# NoBattNVRAM.net
KiCad netlist of a schematic drawn in EAGLE
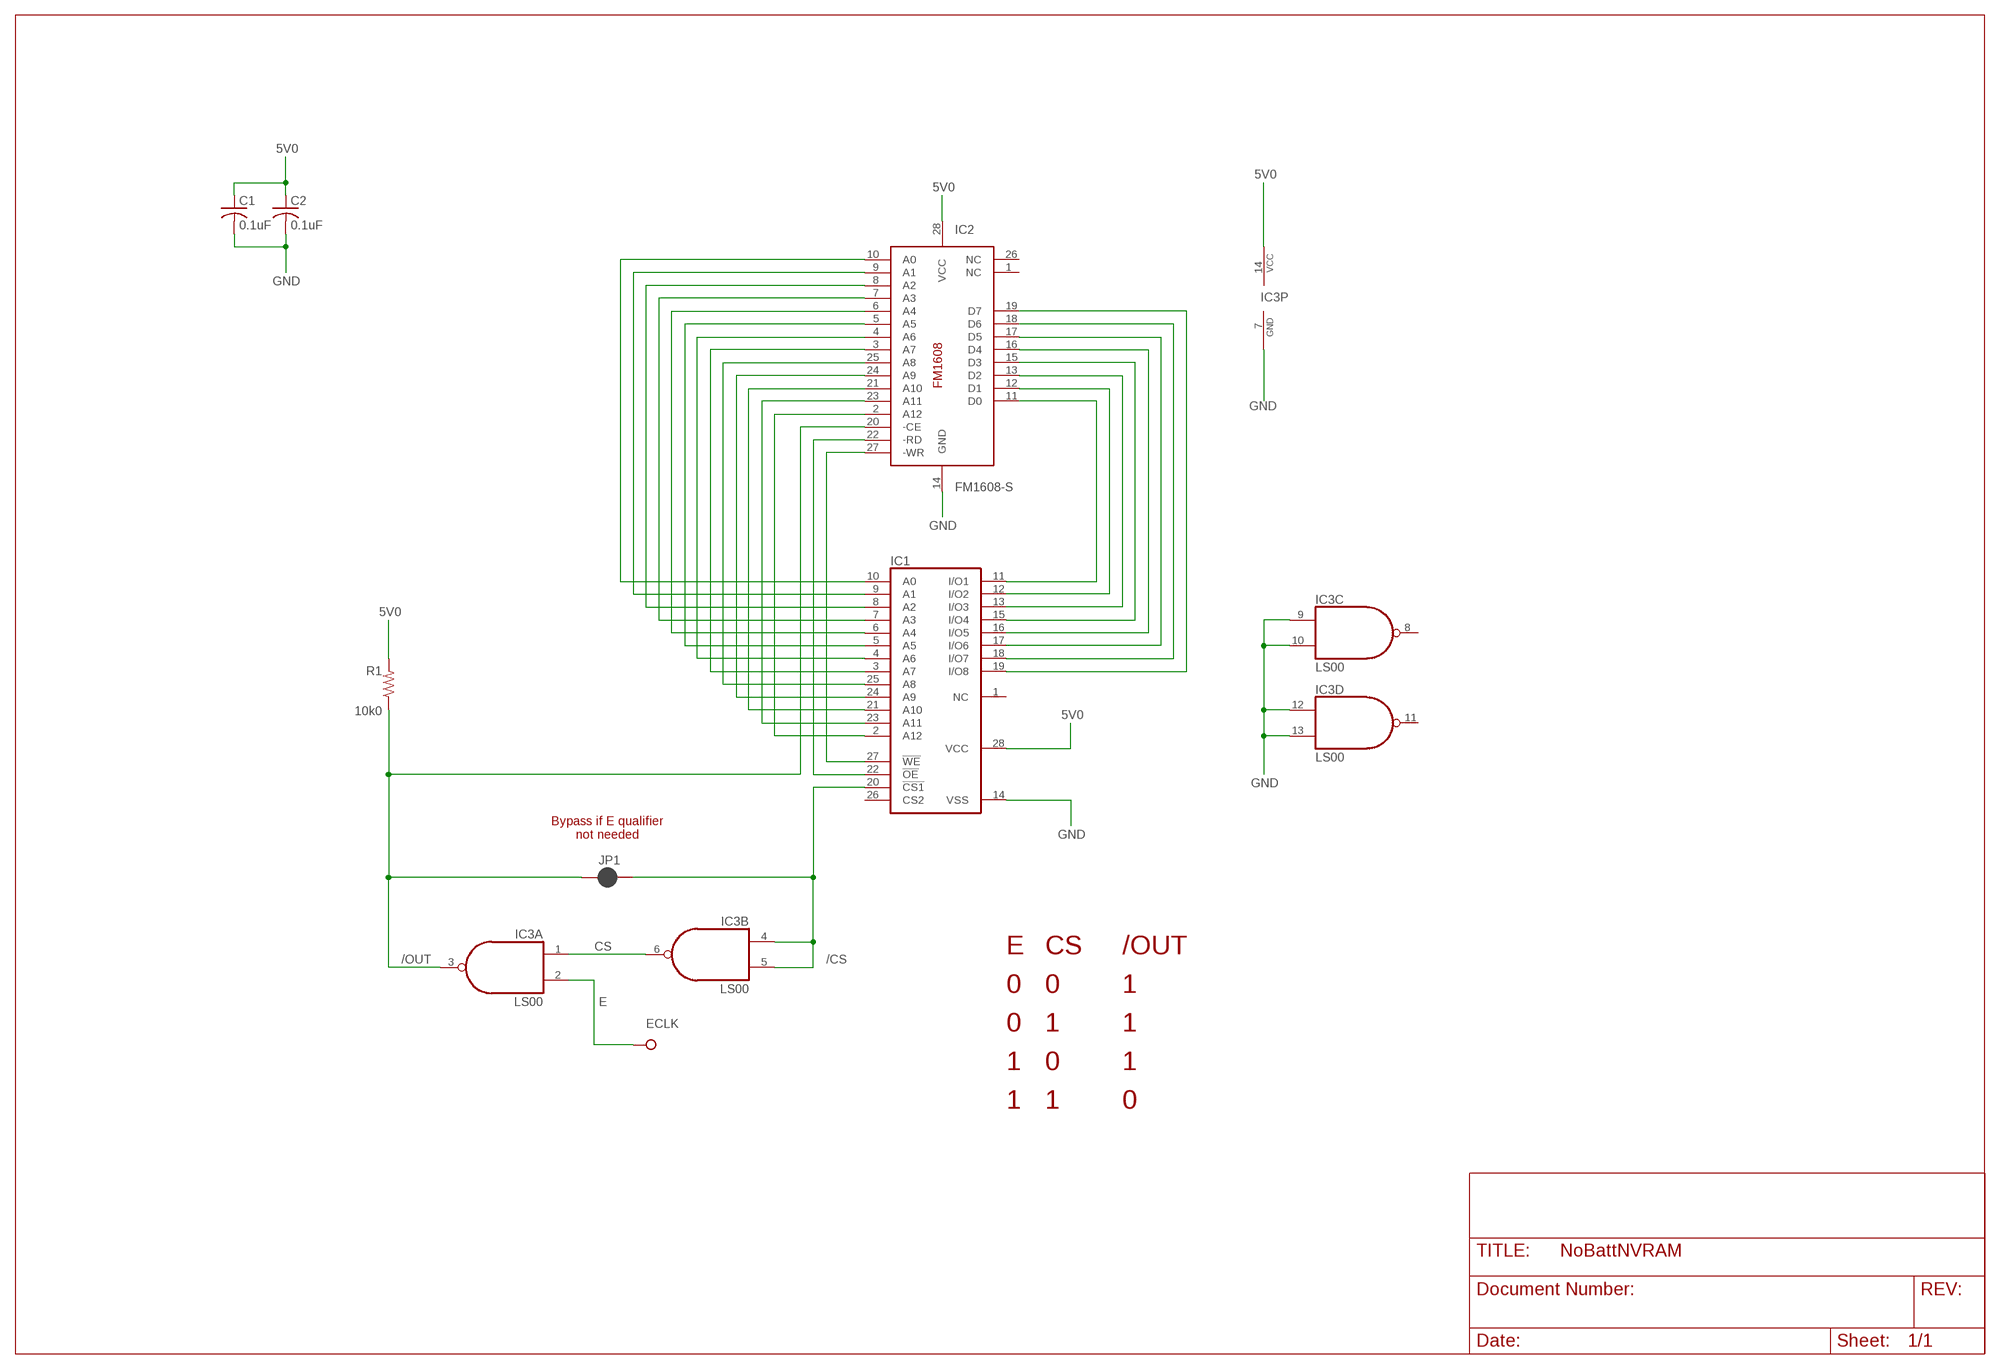
[diagram p0: schematic, sheet 1]

(export (version "E")
  (design (tool "Eeschema 10.0.6"))
  (components
    (comp (ref "C1")
      (value "0.1uF")
      (footprint "eagle-import:C0603K")
      (libsource (lib "eagle-import") (part "C-USC0603K"))
    )
    (comp (ref "C2")
      (value "0.1uF")
      (footprint "eagle-import:C0603K")
      (libsource (lib "eagle-import") (part "C-USC0603K"))
    )
    (comp (ref "ECLK")
      (value "JOE-TP-SHORT")
      (footprint "eagle-import:JOE-TP-PKG")
      (libsource (lib "eagle-import") (part "JOE-TP-SHORT"))
    )
    (comp (ref "IC1")
      (value "6264A")
      (footprint "eagle-import:DIL28-6")
      (libsource (lib "eagle-import") (part "6264A"))
    )
    (comp (ref "IC2")
      (value "FM1608-S")
      (footprint "eagle-import:SO-28W")
      (libsource (lib "eagle-import") (part "FM1608-S"))
    )
    (comp (ref "IC3")
      (value "LS00")
      (footprint "eagle-import:SO14")
      (libsource (lib "eagle-import") (part "7400DLS"))
    )
    (comp (ref "JP1")
      (value "JUMPER-PAD-2-NC_BY_PASTENO-SILK")
      (footprint "eagle-import:PAD-JUMPER-2-NC_BY_PASTE_NO_SILK")
      (libsource (lib "eagle-import") (part "JUMPER-PAD-2-NC_BY_PASTENO-SILK"))
    )
    (comp (ref "R1")
      (value "10k0")
      (footprint "eagle-import:R0805")
      (libsource (lib "eagle-import") (part "R-US_R0805"))
    )
  )
  (nets
    (net (code "1") (name "/5V0") (class "Default")
      (node (ref "C1") (pin "1") (pinfunction "1_1") (pintype "passive"))
      (node (ref "C2") (pin "1") (pinfunction "1_1") (pintype "passive"))
      (node (ref "IC1") (pin "28") (pinfunction "VCC_28") (pintype "power_in"))
      (node (ref "IC2") (pin "28") (pinfunction "VCC_28") (pintype "power_in"))
      (node (ref "IC3") (pin "14") (pinfunction "VCC_14") (pintype "power_in"))
      (node (ref "R1") (pin "2") (pinfunction "2_2") (pintype "passive"))
    )
    (net (code "2") (name "/CS") (class "Default")
      (node (ref "IC3") (pin "1") (pinfunction "I0_1") (pintype "input"))
      (node (ref "IC3") (pin "6") (pinfunction "O_6") (pintype "output"))
    )
    (net (code "3") (name "/E") (class "Default")
      (node (ref "ECLK") (pin "PAD1") (pinfunction "1_PAD1") (pintype "passive"))
      (node (ref "IC3") (pin "2") (pinfunction "I1_2") (pintype "input"))
    )
    (net (code "4") (name "/GND") (class "Default")
      (node (ref "C1") (pin "2") (pinfunction "2_2") (pintype "passive"))
      (node (ref "C2") (pin "2") (pinfunction "2_2") (pintype "passive"))
      (node (ref "IC1") (pin "14") (pinfunction "VSS_14") (pintype "power_in"))
      (node (ref "IC2") (pin "14") (pinfunction "GND_14") (pintype "power_in"))
      (node (ref "IC3") (pin "10") (pinfunction "I1_10") (pintype "input"))
      (node (ref "IC3") (pin "12") (pinfunction "I0_12") (pintype "input"))
      (node (ref "IC3") (pin "13") (pinfunction "I1_13") (pintype "input"))
      (node (ref "IC3") (pin "7") (pinfunction "GND_7") (pintype "power_in"))
      (node (ref "IC3") (pin "9") (pinfunction "I0_9") (pintype "input"))
    )
    (net (code "5") (name "/{slash}CS") (class "Default")
      (node (ref "IC1") (pin "20") (pinfunction "~{CS1}_20") (pintype "input"))
      (node (ref "IC3") (pin "4") (pinfunction "I0_4") (pintype "input"))
      (node (ref "IC3") (pin "5") (pinfunction "I1_5") (pintype "input"))
      (node (ref "JP1") (pin "1") (pinfunction "1_1") (pintype "passive"))
    )
    (net (code "6") (name "/{slash}OUT") (class "Default")
      (node (ref "IC2") (pin "20") (pinfunction "-CE_20") (pintype "input"))
      (node (ref "IC3") (pin "3") (pinfunction "O_3") (pintype "output"))
      (node (ref "JP1") (pin "2") (pinfunction "2_2") (pintype "passive"))
      (node (ref "R1") (pin "1") (pinfunction "1_1") (pintype "passive"))
    )
    (net (code "7") (name "Net-(IC1-A0)") (class "Default")
      (node (ref "IC1") (pin "10") (pinfunction "A0_10") (pintype "input"))
      (node (ref "IC2") (pin "10") (pinfunction "A0_10") (pintype "input"))
    )
    (net (code "8") (name "Net-(IC1-A1)") (class "Default")
      (node (ref "IC1") (pin "9") (pinfunction "A1_9") (pintype "input"))
      (node (ref "IC2") (pin "9") (pinfunction "A1_9") (pintype "input"))
    )
    (net (code "9") (name "Net-(IC1-A2)") (class "Default")
      (node (ref "IC1") (pin "8") (pinfunction "A2_8") (pintype "input"))
      (node (ref "IC2") (pin "8") (pinfunction "A2_8") (pintype "input"))
    )
    (net (code "10") (name "Net-(IC1-A3)") (class "Default")
      (node (ref "IC1") (pin "7") (pinfunction "A3_7") (pintype "input"))
      (node (ref "IC2") (pin "7") (pinfunction "A3_7") (pintype "input"))
    )
    (net (code "11") (name "Net-(IC1-A4)") (class "Default")
      (node (ref "IC1") (pin "6") (pinfunction "A4_6") (pintype "input"))
      (node (ref "IC2") (pin "6") (pinfunction "A4_6") (pintype "input"))
    )
    (net (code "12") (name "Net-(IC1-A5)") (class "Default")
      (node (ref "IC1") (pin "5") (pinfunction "A5_5") (pintype "input"))
      (node (ref "IC2") (pin "5") (pinfunction "A5_5") (pintype "input"))
    )
    (net (code "13") (name "Net-(IC1-A6)") (class "Default")
      (node (ref "IC1") (pin "4") (pinfunction "A6_4") (pintype "input"))
      (node (ref "IC2") (pin "4") (pinfunction "A6_4") (pintype "input"))
    )
    (net (code "14") (name "Net-(IC1-A7)") (class "Default")
      (node (ref "IC1") (pin "3") (pinfunction "A7_3") (pintype "input"))
      (node (ref "IC2") (pin "3") (pinfunction "A7_3") (pintype "input"))
    )
    (net (code "15") (name "Net-(IC1-A8)") (class "Default")
      (node (ref "IC1") (pin "25") (pinfunction "A8_25") (pintype "input"))
      (node (ref "IC2") (pin "25") (pinfunction "A8_25") (pintype "input"))
    )
    (net (code "16") (name "Net-(IC1-A9)") (class "Default")
      (node (ref "IC1") (pin "24") (pinfunction "A9_24") (pintype "input"))
      (node (ref "IC2") (pin "24") (pinfunction "A9_24") (pintype "input"))
    )
    (net (code "17") (name "Net-(IC1-A10)") (class "Default")
      (node (ref "IC1") (pin "21") (pinfunction "A10_21") (pintype "input"))
      (node (ref "IC2") (pin "21") (pinfunction "A10_21") (pintype "input"))
    )
    (net (code "18") (name "Net-(IC1-A11)") (class "Default")
      (node (ref "IC1") (pin "23") (pinfunction "A11_23") (pintype "input"))
      (node (ref "IC2") (pin "23") (pinfunction "A11_23") (pintype "input"))
    )
    (net (code "19") (name "Net-(IC1-A12)") (class "Default")
      (node (ref "IC1") (pin "2") (pinfunction "A12_2") (pintype "input"))
      (node (ref "IC2") (pin "2") (pinfunction "A12_2") (pintype "input"))
    )
    (net (code "20") (name "Net-(IC1-I{slash}O1)") (class "Default")
      (node (ref "IC1") (pin "11") (pinfunction "I/O1_11") (pintype "bidirectional"))
      (node (ref "IC2") (pin "11") (pinfunction "D0_11") (pintype "bidirectional"))
    )
    (net (code "21") (name "Net-(IC1-I{slash}O2)") (class "Default")
      (node (ref "IC1") (pin "12") (pinfunction "I/O2_12") (pintype "bidirectional"))
      (node (ref "IC2") (pin "12") (pinfunction "D1_12") (pintype "bidirectional"))
    )
    (net (code "22") (name "Net-(IC1-I{slash}O3)") (class "Default")
      (node (ref "IC1") (pin "13") (pinfunction "I/O3_13") (pintype "bidirectional"))
      (node (ref "IC2") (pin "13") (pinfunction "D2_13") (pintype "bidirectional"))
    )
    (net (code "23") (name "Net-(IC1-I{slash}O4)") (class "Default")
      (node (ref "IC1") (pin "15") (pinfunction "I/O4_15") (pintype "bidirectional"))
      (node (ref "IC2") (pin "15") (pinfunction "D3_15") (pintype "bidirectional"))
    )
    (net (code "24") (name "Net-(IC1-I{slash}O5)") (class "Default")
      (node (ref "IC1") (pin "16") (pinfunction "I/O5_16") (pintype "bidirectional"))
      (node (ref "IC2") (pin "16") (pinfunction "D4_16") (pintype "bidirectional"))
    )
    (net (code "25") (name "Net-(IC1-I{slash}O6)") (class "Default")
      (node (ref "IC1") (pin "17") (pinfunction "I/O6_17") (pintype "bidirectional"))
      (node (ref "IC2") (pin "17") (pinfunction "D5_17") (pintype "bidirectional"))
    )
    (net (code "26") (name "Net-(IC1-I{slash}O7)") (class "Default")
      (node (ref "IC1") (pin "18") (pinfunction "I/O7_18") (pintype "bidirectional"))
      (node (ref "IC2") (pin "18") (pinfunction "D6_18") (pintype "bidirectional"))
    )
    (net (code "27") (name "Net-(IC1-I{slash}O8)") (class "Default")
      (node (ref "IC1") (pin "19") (pinfunction "I/O8_19") (pintype "bidirectional"))
      (node (ref "IC2") (pin "19") (pinfunction "D7_19") (pintype "bidirectional"))
    )
    (net (code "28") (name "Net-(IC1-~{OE})") (class "Default")
      (node (ref "IC1") (pin "22") (pinfunction "~{OE}_22") (pintype "input"))
      (node (ref "IC2") (pin "22") (pinfunction "-RD_22") (pintype "input"))
    )
    (net (code "29") (name "Net-(IC1-~{WE})") (class "Default")
      (node (ref "IC1") (pin "27") (pinfunction "~{WE}_27") (pintype "input"))
      (node (ref "IC2") (pin "27") (pinfunction "-WR_27") (pintype "input"))
    )
    (net (code "30") (name "unconnected-(IC1-CS2-Pad26)") (class "Default")
      (node (ref "IC1") (pin "26") (pinfunction "CS2_26") (pintype "input"))
    )
    (net (code "31") (name "unconnected-(IC1-NC-Pad1)") (class "Default")
      (node (ref "IC1") (pin "1") (pinfunction "NC_1") (pintype "no_connect"))
    )
    (net (code "32") (name "unconnected-(IC2-NC-Pad1)") (class "Default")
      (node (ref "IC2") (pin "1") (pinfunction "NC_1") (pintype "passive"))
    )
    (net (code "33") (name "unconnected-(IC2-NC-Pad26)") (class "Default")
      (node (ref "IC2") (pin "26") (pinfunction "NC_26") (pintype "passive"))
    )
    (net (code "34") (name "unconnected-(IC3C-O-Pad8)") (class "Default")
      (node (ref "IC3") (pin "8") (pinfunction "O_8") (pintype "output"))
    )
    (net (code "35") (name "unconnected-(IC3D-O-Pad11)") (class "Default")
      (node (ref "IC3") (pin "11") (pinfunction "O_11") (pintype "output"))
    )
  )
)
